# PCB-UHB-MIX1.net
KiCad netlist of a schematic drawn in EAGLE
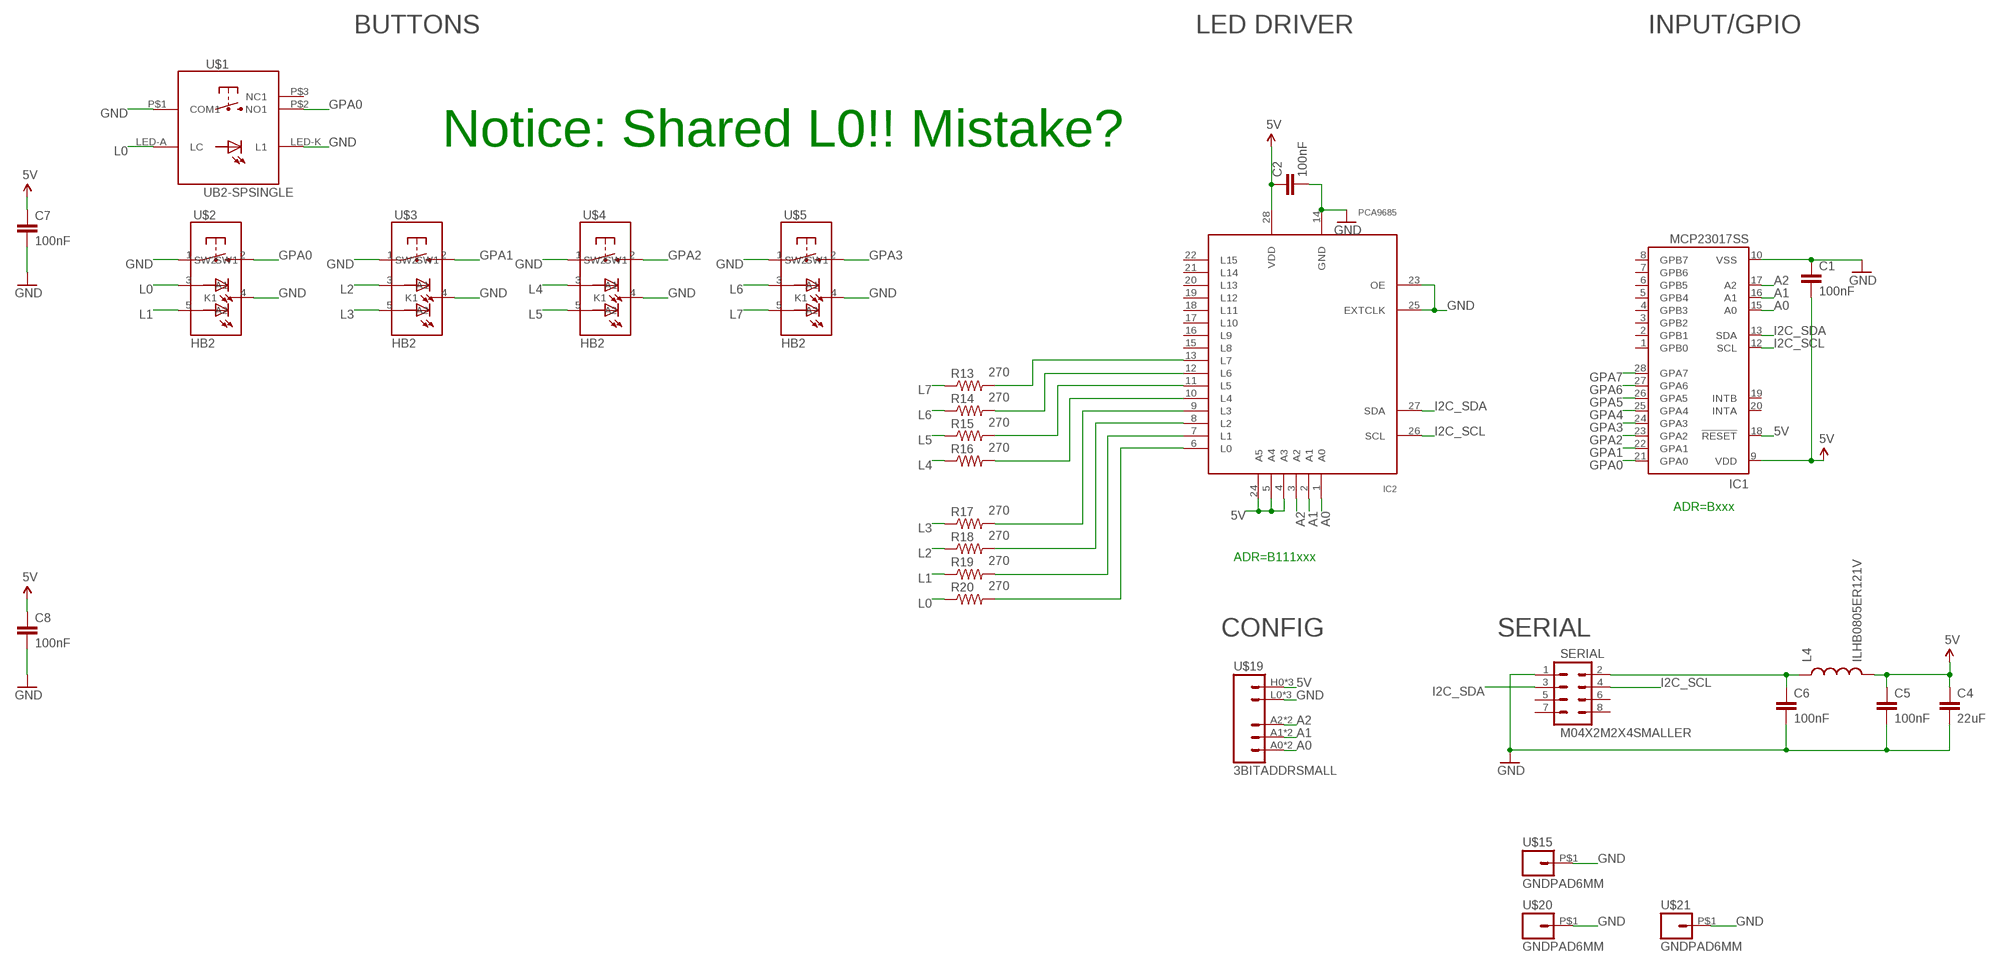
[diagram p0: schematic, sheet 1]

(export (version "E")
  (design (tool "Eeschema 10.0.6"))
  (components
    (comp (ref "C1")
      (value "100nF")
      (footprint "eagle-import:0603-CAP")
      (libsource (lib "eagle-import") (part "CAP0603-CAP"))
    )
    (comp (ref "C2")
      (value "100nF")
      (footprint "eagle-import:0603-CAP")
      (libsource (lib "eagle-import") (part "CAP0603-CAP"))
    )
    (comp (ref "C4")
      (value "22uF")
      (footprint "eagle-import:0805")
      (libsource (lib "eagle-import") (part "CAP0805"))
    )
    (comp (ref "C5")
      (value "100nF")
      (footprint "eagle-import:0603-CAP")
      (libsource (lib "eagle-import") (part "CAP0603-CAP"))
    )
    (comp (ref "C6")
      (value "100nF")
      (footprint "eagle-import:0603-CAP")
      (libsource (lib "eagle-import") (part "CAP0603-CAP"))
    )
    (comp (ref "C7")
      (value "100nF")
      (footprint "eagle-import:0603-CAP")
      (libsource (lib "eagle-import") (part "CAP0603-CAP"))
    )
    (comp (ref "C8")
      (value "100nF")
      (footprint "eagle-import:0603-CAP")
      (libsource (lib "eagle-import") (part "CAP0603-CAP"))
    )
    (comp (ref "IC1")
      (value "MCP23017SS")
      (footprint "eagle-import:SSOP28")
      (fields
        (field (name "MF") "MICROCHIP")
        (field (name "MPN") "MCP23017-E/SS")
        (field (name "MPN_1") "MCP23017-E/SS")
        (field (name "OC_FARNELL") "1467674")
        (field (name "OC_NEWARK") "31K2960")
      )
      (libsource (lib "eagle-import") (part "MCP23017SS"))
    )
    (comp (ref "IC2")
      (value "PCA9685")
      (footprint "eagle-import:TSSOP28")
      (libsource (lib "eagle-import") (part "PCA9685"))
    )
    (comp (ref "L4")
      (value "ILHB0805ER121V")
      (footprint "eagle-import:0805")
      (libsource (lib "eagle-import") (part "INDUCTOR0805"))
    )
    (comp (ref "R13")
      (value "270")
      (footprint "eagle-import:0603-RES")
      (libsource (lib "eagle-import") (part "RESISTOR0603-RES"))
    )
    (comp (ref "R14")
      (value "270")
      (footprint "eagle-import:0603-RES")
      (libsource (lib "eagle-import") (part "RESISTOR0603-RES"))
    )
    (comp (ref "R15")
      (value "270")
      (footprint "eagle-import:0603-RES")
      (libsource (lib "eagle-import") (part "RESISTOR0603-RES"))
    )
    (comp (ref "R16")
      (value "270")
      (footprint "eagle-import:0603-RES")
      (libsource (lib "eagle-import") (part "RESISTOR0603-RES"))
    )
    (comp (ref "R17")
      (value "270")
      (footprint "eagle-import:0603-RES")
      (libsource (lib "eagle-import") (part "RESISTOR0603-RES"))
    )
    (comp (ref "R18")
      (value "270")
      (footprint "eagle-import:0603-RES")
      (libsource (lib "eagle-import") (part "RESISTOR0603-RES"))
    )
    (comp (ref "R19")
      (value "270")
      (footprint "eagle-import:0603-RES")
      (libsource (lib "eagle-import") (part "RESISTOR0603-RES"))
    )
    (comp (ref "R20")
      (value "270")
      (footprint "eagle-import:0603-RES")
      (libsource (lib "eagle-import") (part "RESISTOR0603-RES"))
    )
    (comp (ref "SERIAL")
      (value "M04X2M2X4SMALLER")
      (footprint "eagle-import:M2X4SMALLER")
      (libsource (lib "eagle-import") (part "M04X2M2X4SMALLER"))
    )
    (comp (ref "U$1")
      (value "UB2-SPSINGLE")
      (footprint "eagle-import:UB2-SPSINGLE")
      (libsource (lib "eagle-import") (part "UB2-SPSINGLE"))
    )
    (comp (ref "U$2")
      (value "HB2")
      (footprint "eagle-import:HB2")
      (libsource (lib "eagle-import") (part "HB2"))
    )
    (comp (ref "U$3")
      (value "HB2")
      (footprint "eagle-import:HB2")
      (libsource (lib "eagle-import") (part "HB2"))
    )
    (comp (ref "U$4")
      (value "HB2")
      (footprint "eagle-import:HB2")
      (libsource (lib "eagle-import") (part "HB2"))
    )
    (comp (ref "U$5")
      (value "HB2")
      (footprint "eagle-import:HB2")
      (libsource (lib "eagle-import") (part "HB2"))
    )
    (comp (ref "U$15")
      (value "GNDPAD6MM")
      (footprint "eagle-import:3.2MMPAD6MM")
      (libsource (lib "eagle-import") (part "GNDPAD6MM"))
    )
    (comp (ref "U$19")
      (value "3BITADDRSMALL")
      (footprint "eagle-import:3BITADDR_SMALL")
      (libsource (lib "eagle-import") (part "3BITADDRSMALL"))
    )
    (comp (ref "U$20")
      (value "GNDPAD6MM")
      (footprint "eagle-import:3.2MMPAD6MM")
      (libsource (lib "eagle-import") (part "GNDPAD6MM"))
    )
    (comp (ref "U$21")
      (value "GNDPAD6MM")
      (footprint "eagle-import:3.2MMPAD6MM")
      (libsource (lib "eagle-import") (part "GNDPAD6MM"))
    )
  )
  (nets
    (net (code "1") (name "5V") (class "Default")
      (node (ref "C1") (pin "2") (pinfunction "2_2") (pintype "passive"))
      (node (ref "C2") (pin "1") (pinfunction "1_1") (pintype "passive"))
      (node (ref "C4") (pin "1") (pinfunction "1_1") (pintype "passive"))
      (node (ref "C5") (pin "1") (pinfunction "1_1") (pintype "passive"))
      (node (ref "C7") (pin "1") (pinfunction "1_1") (pintype "passive"))
      (node (ref "C8") (pin "1") (pinfunction "1_1") (pintype "passive"))
      (node (ref "IC1") (pin "18") (pinfunction "~{RESET}_18") (pintype "input"))
      (node (ref "IC1") (pin "9") (pinfunction "VDD_9") (pintype "power_in"))
      (node (ref "IC2") (pin "24") (pinfunction "A5_24") (pintype "input"))
      (node (ref "IC2") (pin "28") (pinfunction "VDD_28") (pintype "power_in"))
      (node (ref "IC2") (pin "4") (pinfunction "A3_4") (pintype "input"))
      (node (ref "IC2") (pin "5") (pinfunction "A4_5") (pintype "input"))
      (node (ref "L4") (pin "2") (pinfunction "2_2") (pintype "passive"))
      (node (ref "U$19") (pin "H0") (pinfunction "VCC_H0") (pintype "passive"))
      (node (ref "U$19") (pin "H1") (pinfunction "VCC_H1") (pintype "passive"))
      (node (ref "U$19") (pin "H2") (pinfunction "VCC_H2") (pintype "passive"))
    )
    (net (code "2") (name "A0") (class "Default")
      (node (ref "IC1") (pin "15") (pinfunction "A0_15") (pintype "input"))
      (node (ref "IC2") (pin "1") (pinfunction "A0_1") (pintype "input"))
      (node (ref "U$19") (pin "A0") (pinfunction "A0_A0") (pintype "passive"))
      (node (ref "U$19") (pin "AS0") (pinfunction "A0_AS0") (pintype "passive"))
    )
    (net (code "3") (name "A1") (class "Default")
      (node (ref "IC1") (pin "16") (pinfunction "A1_16") (pintype "input"))
      (node (ref "IC2") (pin "2") (pinfunction "A1_2") (pintype "input"))
      (node (ref "U$19") (pin "A1") (pinfunction "A1_A1") (pintype "passive"))
      (node (ref "U$19") (pin "AS1") (pinfunction "A1_AS1") (pintype "passive"))
    )
    (net (code "4") (name "A2") (class "Default")
      (node (ref "IC1") (pin "17") (pinfunction "A2_17") (pintype "input"))
      (node (ref "IC2") (pin "3") (pinfunction "A2_3") (pintype "input"))
      (node (ref "U$19") (pin "A2") (pinfunction "A2_A2") (pintype "passive"))
      (node (ref "U$19") (pin "AS2") (pinfunction "A2_AS2") (pintype "passive"))
    )
    (net (code "5") (name "GND") (class "Default")
      (node (ref "C1") (pin "1") (pinfunction "1_1") (pintype "passive"))
      (node (ref "C2") (pin "2") (pinfunction "2_2") (pintype "passive"))
      (node (ref "C4") (pin "2") (pinfunction "2_2") (pintype "passive"))
      (node (ref "C5") (pin "2") (pinfunction "2_2") (pintype "passive"))
      (node (ref "C6") (pin "2") (pinfunction "2_2") (pintype "passive"))
      (node (ref "C7") (pin "2") (pinfunction "2_2") (pintype "passive"))
      (node (ref "C8") (pin "2") (pinfunction "2_2") (pintype "passive"))
      (node (ref "IC1") (pin "10") (pinfunction "VSS_10") (pintype "power_in"))
      (node (ref "IC2") (pin "14") (pinfunction "GND_14") (pintype "power_in"))
      (node (ref "IC2") (pin "23") (pinfunction "OE_23") (pintype "input"))
      (node (ref "IC2") (pin "25") (pinfunction "EXTCLK_25") (pintype "input"))
      (node (ref "SERIAL") (pin "1") (pinfunction "1_1") (pintype "passive"))
      (node (ref "U$1") (pin "LED-K") (pinfunction "L1_LED-K") (pintype "bidirectional"))
      (node (ref "U$1") (pin "P$1") (pinfunction "COM1_P$1") (pintype "bidirectional"))
      (node (ref "U$15") (pin "P$1") (pinfunction "1_P$1") (pintype "passive"))
      (node (ref "U$19") (pin "L0") (pinfunction "GND_L0") (pintype "passive"))
      (node (ref "U$19") (pin "L1") (pinfunction "GND_L1") (pintype "passive"))
      (node (ref "U$19") (pin "L2") (pinfunction "GND_L2") (pintype "passive"))
      (node (ref "U$2") (pin "1") (pinfunction "SW1_1") (pintype "bidirectional"))
      (node (ref "U$2") (pin "4") (pinfunction "K1_4") (pintype "bidirectional"))
      (node (ref "U$20") (pin "P$1") (pinfunction "1_P$1") (pintype "passive"))
      (node (ref "U$21") (pin "P$1") (pinfunction "1_P$1") (pintype "passive"))
      (node (ref "U$3") (pin "1") (pinfunction "SW1_1") (pintype "bidirectional"))
      (node (ref "U$3") (pin "4") (pinfunction "K1_4") (pintype "bidirectional"))
      (node (ref "U$4") (pin "1") (pinfunction "SW1_1") (pintype "bidirectional"))
      (node (ref "U$4") (pin "4") (pinfunction "K1_4") (pintype "bidirectional"))
      (node (ref "U$5") (pin "1") (pinfunction "SW1_1") (pintype "bidirectional"))
      (node (ref "U$5") (pin "4") (pinfunction "K1_4") (pintype "bidirectional"))
    )
    (net (code "6") (name "GPA0") (class "Default")
      (node (ref "IC1") (pin "21") (pinfunction "GPA0_21") (pintype "bidirectional"))
      (node (ref "U$1") (pin "P$2") (pinfunction "NO1_P$2") (pintype "bidirectional"))
      (node (ref "U$2") (pin "2") (pinfunction "SW2_2") (pintype "bidirectional"))
    )
    (net (code "7") (name "GPA1") (class "Default")
      (node (ref "IC1") (pin "22") (pinfunction "GPA1_22") (pintype "bidirectional"))
      (node (ref "U$3") (pin "2") (pinfunction "SW2_2") (pintype "bidirectional"))
    )
    (net (code "8") (name "GPA2") (class "Default")
      (node (ref "IC1") (pin "23") (pinfunction "GPA2_23") (pintype "bidirectional"))
      (node (ref "U$4") (pin "2") (pinfunction "SW2_2") (pintype "bidirectional"))
    )
    (net (code "9") (name "GPA3") (class "Default")
      (node (ref "IC1") (pin "24") (pinfunction "GPA3_24") (pintype "bidirectional"))
      (node (ref "U$5") (pin "2") (pinfunction "SW2_2") (pintype "bidirectional"))
    )
    (net (code "10") (name "GPA4") (class "Default")
      (node (ref "IC1") (pin "25") (pinfunction "GPA4_25") (pintype "bidirectional"))
    )
    (net (code "11") (name "GPA5") (class "Default")
      (node (ref "IC1") (pin "26") (pinfunction "GPA5_26") (pintype "bidirectional"))
    )
    (net (code "12") (name "GPA6") (class "Default")
      (node (ref "IC1") (pin "27") (pinfunction "GPA6_27") (pintype "bidirectional"))
    )
    (net (code "13") (name "GPA7") (class "Default")
      (node (ref "IC1") (pin "28") (pinfunction "GPA7_28") (pintype "bidirectional"))
    )
    (net (code "14") (name "I2C_SCL") (class "Default")
      (node (ref "IC1") (pin "12") (pinfunction "SCL_12") (pintype "input"))
      (node (ref "IC2") (pin "26") (pinfunction "SCL_26") (pintype "input"))
      (node (ref "SERIAL") (pin "4") (pinfunction "4_4") (pintype "passive"))
    )
    (net (code "15") (name "I2C_SDA") (class "Default")
      (node (ref "IC1") (pin "13") (pinfunction "SDA_13") (pintype "bidirectional"))
      (node (ref "IC2") (pin "27") (pinfunction "SDA_27") (pintype "input"))
      (node (ref "SERIAL") (pin "3") (pinfunction "3_3") (pintype "passive"))
    )
    (net (code "16") (name "L0") (class "Default")
      (node (ref "R20") (pin "1") (pinfunction "1_1") (pintype "passive"))
      (node (ref "U$1") (pin "LED-A") (pinfunction "LC_LED-A") (pintype "bidirectional"))
      (node (ref "U$2") (pin "3") (pinfunction "A1_3") (pintype "bidirectional"))
    )
    (net (code "17") (name "L1") (class "Default")
      (node (ref "R19") (pin "1") (pinfunction "1_1") (pintype "passive"))
      (node (ref "U$2") (pin "5") (pinfunction "A2_5") (pintype "bidirectional"))
    )
    (net (code "18") (name "L2") (class "Default")
      (node (ref "R18") (pin "1") (pinfunction "1_1") (pintype "passive"))
      (node (ref "U$3") (pin "3") (pinfunction "A1_3") (pintype "bidirectional"))
    )
    (net (code "19") (name "L3") (class "Default")
      (node (ref "R17") (pin "1") (pinfunction "1_1") (pintype "passive"))
      (node (ref "U$3") (pin "5") (pinfunction "A2_5") (pintype "bidirectional"))
    )
    (net (code "20") (name "L4") (class "Default")
      (node (ref "R16") (pin "1") (pinfunction "1_1") (pintype "passive"))
      (node (ref "U$4") (pin "3") (pinfunction "A1_3") (pintype "bidirectional"))
    )
    (net (code "21") (name "L5") (class "Default")
      (node (ref "R15") (pin "1") (pinfunction "1_1") (pintype "passive"))
      (node (ref "U$4") (pin "5") (pinfunction "A2_5") (pintype "bidirectional"))
    )
    (net (code "22") (name "L6") (class "Default")
      (node (ref "R14") (pin "1") (pinfunction "1_1") (pintype "passive"))
      (node (ref "U$5") (pin "3") (pinfunction "A1_3") (pintype "bidirectional"))
    )
    (net (code "23") (name "L7") (class "Default")
      (node (ref "R13") (pin "1") (pinfunction "1_1") (pintype "passive"))
      (node (ref "U$5") (pin "5") (pinfunction "A2_5") (pintype "bidirectional"))
    )
    (net (code "24") (name "Net-(C6-Pad1)") (class "Default")
      (node (ref "C6") (pin "1") (pinfunction "1_1") (pintype "passive"))
      (node (ref "L4") (pin "1") (pinfunction "1_1") (pintype "passive"))
      (node (ref "SERIAL") (pin "2") (pinfunction "2_2") (pintype "passive"))
    )
    (net (code "25") (name "Net-(IC2-L0)") (class "Default")
      (node (ref "IC2") (pin "6") (pinfunction "L0_6") (pintype "output"))
      (node (ref "R20") (pin "2") (pinfunction "2_2") (pintype "passive"))
    )
    (net (code "26") (name "Net-(IC2-L1)") (class "Default")
      (node (ref "IC2") (pin "7") (pinfunction "L1_7") (pintype "output"))
      (node (ref "R19") (pin "2") (pinfunction "2_2") (pintype "passive"))
    )
    (net (code "27") (name "Net-(IC2-L2)") (class "Default")
      (node (ref "IC2") (pin "8") (pinfunction "L2_8") (pintype "output"))
      (node (ref "R18") (pin "2") (pinfunction "2_2") (pintype "passive"))
    )
    (net (code "28") (name "Net-(IC2-L3)") (class "Default")
      (node (ref "IC2") (pin "9") (pinfunction "L3_9") (pintype "output"))
      (node (ref "R17") (pin "2") (pinfunction "2_2") (pintype "passive"))
    )
    (net (code "29") (name "Net-(IC2-L4)") (class "Default")
      (node (ref "IC2") (pin "10") (pinfunction "L4_10") (pintype "output"))
      (node (ref "R16") (pin "2") (pinfunction "2_2") (pintype "passive"))
    )
    (net (code "30") (name "Net-(IC2-L5)") (class "Default")
      (node (ref "IC2") (pin "11") (pinfunction "L5_11") (pintype "output"))
      (node (ref "R15") (pin "2") (pinfunction "2_2") (pintype "passive"))
    )
    (net (code "31") (name "Net-(IC2-L6)") (class "Default")
      (node (ref "IC2") (pin "12") (pinfunction "L6_12") (pintype "output"))
      (node (ref "R14") (pin "2") (pinfunction "2_2") (pintype "passive"))
    )
    (net (code "32") (name "Net-(IC2-L7)") (class "Default")
      (node (ref "IC2") (pin "13") (pinfunction "L7_13") (pintype "output"))
      (node (ref "R13") (pin "2") (pinfunction "2_2") (pintype "passive"))
    )
    (net (code "33") (name "unconnected-(IC1-GPB0-Pad1)") (class "Default")
      (node (ref "IC1") (pin "1") (pinfunction "GPB0_1") (pintype "bidirectional"))
    )
    (net (code "34") (name "unconnected-(IC1-GPB1-Pad2)") (class "Default")
      (node (ref "IC1") (pin "2") (pinfunction "GPB1_2") (pintype "bidirectional"))
    )
    (net (code "35") (name "unconnected-(IC1-GPB2-Pad3)") (class "Default")
      (node (ref "IC1") (pin "3") (pinfunction "GPB2_3") (pintype "bidirectional"))
    )
    (net (code "36") (name "unconnected-(IC1-GPB3-Pad4)") (class "Default")
      (node (ref "IC1") (pin "4") (pinfunction "GPB3_4") (pintype "bidirectional"))
    )
    (net (code "37") (name "unconnected-(IC1-GPB4-Pad5)") (class "Default")
      (node (ref "IC1") (pin "5") (pinfunction "GPB4_5") (pintype "bidirectional"))
    )
    (net (code "38") (name "unconnected-(IC1-GPB5-Pad6)") (class "Default")
      (node (ref "IC1") (pin "6") (pinfunction "GPB5_6") (pintype "bidirectional"))
    )
    (net (code "39") (name "unconnected-(IC1-GPB6-Pad7)") (class "Default")
      (node (ref "IC1") (pin "7") (pinfunction "GPB6_7") (pintype "bidirectional"))
    )
    (net (code "40") (name "unconnected-(IC1-GPB7-Pad8)") (class "Default")
      (node (ref "IC1") (pin "8") (pinfunction "GPB7_8") (pintype "bidirectional"))
    )
    (net (code "41") (name "unconnected-(IC1-INTA-Pad20)") (class "Default")
      (node (ref "IC1") (pin "20") (pinfunction "INTA_20") (pintype "output"))
    )
    (net (code "42") (name "unconnected-(IC1-INTB-Pad19)") (class "Default")
      (node (ref "IC1") (pin "19") (pinfunction "INTB_19") (pintype "output"))
    )
    (net (code "43") (name "unconnected-(IC2-L8-Pad15)") (class "Default")
      (node (ref "IC2") (pin "15") (pinfunction "L8_15") (pintype "output"))
    )
    (net (code "44") (name "unconnected-(IC2-L9-Pad16)") (class "Default")
      (node (ref "IC2") (pin "16") (pinfunction "L9_16") (pintype "output"))
    )
    (net (code "45") (name "unconnected-(IC2-L10-Pad17)") (class "Default")
      (node (ref "IC2") (pin "17") (pinfunction "L10_17") (pintype "output"))
    )
    (net (code "46") (name "unconnected-(IC2-L11-Pad18)") (class "Default")
      (node (ref "IC2") (pin "18") (pinfunction "L11_18") (pintype "output"))
    )
    (net (code "47") (name "unconnected-(IC2-L12-Pad19)") (class "Default")
      (node (ref "IC2") (pin "19") (pinfunction "L12_19") (pintype "output"))
    )
    (net (code "48") (name "unconnected-(IC2-L13-Pad20)") (class "Default")
      (node (ref "IC2") (pin "20") (pinfunction "L13_20") (pintype "output"))
    )
    (net (code "49") (name "unconnected-(IC2-L14-Pad21)") (class "Default")
      (node (ref "IC2") (pin "21") (pinfunction "L14_21") (pintype "output"))
    )
    (net (code "50") (name "unconnected-(IC2-L15-Pad22)") (class "Default")
      (node (ref "IC2") (pin "22") (pinfunction "L15_22") (pintype "output"))
    )
    (net (code "51") (name "unconnected-(SERIAL-Pad5)") (class "Default")
      (node (ref "SERIAL") (pin "5") (pinfunction "5_5") (pintype "passive"))
    )
    (net (code "52") (name "unconnected-(SERIAL-Pad6)") (class "Default")
      (node (ref "SERIAL") (pin "6") (pinfunction "6_6") (pintype "passive"))
    )
    (net (code "53") (name "unconnected-(SERIAL-Pad7)") (class "Default")
      (node (ref "SERIAL") (pin "7") (pinfunction "7_7") (pintype "passive"))
    )
    (net (code "54") (name "unconnected-(SERIAL-Pad8)") (class "Default")
      (node (ref "SERIAL") (pin "8") (pinfunction "8_8") (pintype "passive"))
    )
    (net (code "55") (name "unconnected-(U$1-NC1-PadP$3)") (class "Default")
      (node (ref "U$1") (pin "P$3") (pinfunction "NC1_P$3") (pintype "bidirectional"))
    )
  )
)
